# H05R2x_Frontend_1.net
KiCad netlist of a schematic drawn in Altium Designer
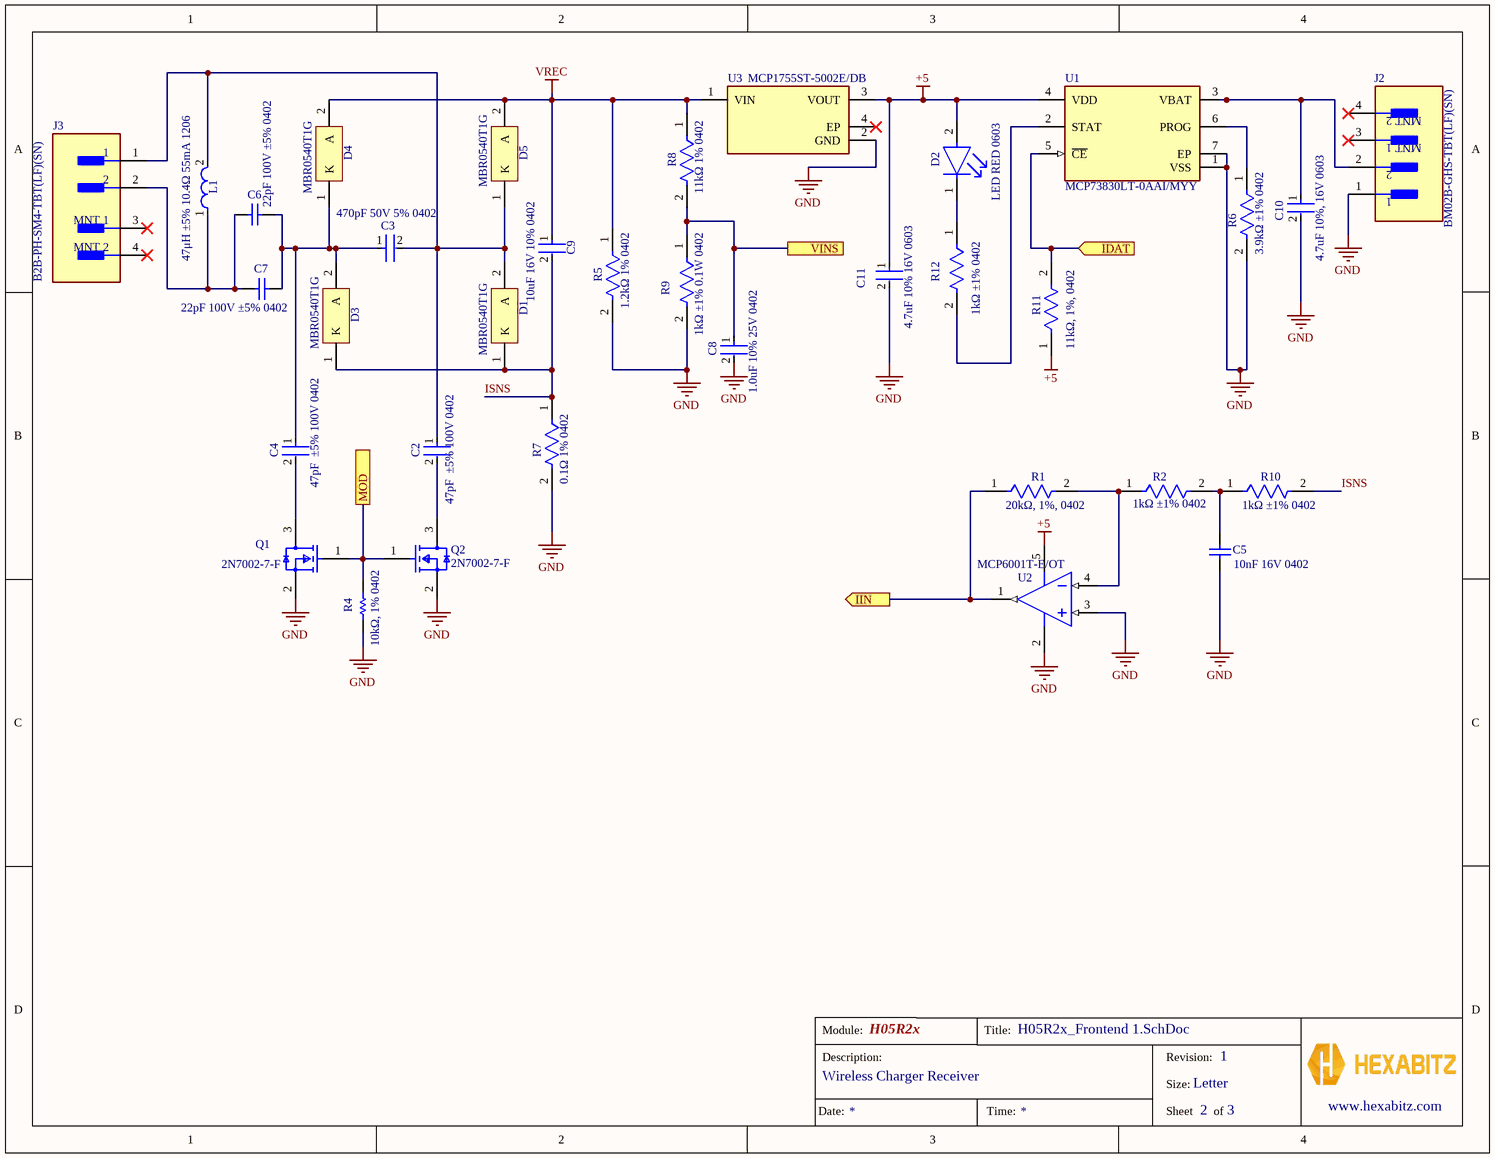
[diagram p0: H05R2x_Frontend 1.SchDoc]

(export (version "E")
  (design (tool "Eeschema 10.0.6"))
  (components
    (comp (ref "C2")
      (value "47pF  ±5% 100V 0402")
      (footprint "FP-GQM155-0_05-IPC_A")
      (description "Ceramic Capacitor 47pF  ±5% 100VDC C0G 0402 Paper T/R")
      (fields (field (name "TOLERANCE") "5%"))
      (libsource (lib "Altium Content Vault") (part "11868f565c42a9108669ba33697ecf6"))
    )
    (comp (ref "C3")
      (value "470pF 50V 5% 0402")
      (footprint "FP-C0402-BB-MFG")
      (description "C0402 470 pF C0G 0.05 50 V")
      (fields
        (field (name "MANUFACTURER PART NUMBER") "C0402C471J5GAC")
        (field (name "MANUFACTURER") "Kemet")
      )
      (libsource (lib "Altium Content Vault") (part "b4654b650e69147ec39a6b967a45e02"))
    )
    (comp (ref "C4")
      (value "47pF  ±5% 100V 0402")
      (footprint "FP-GQM155-0_05-IPC_A")
      (description "Ceramic Capacitor 47pF  ±5% 100VDC C0G 0402 Paper T/R")
      (fields (field (name "TOLERANCE") "5%"))
      (libsource (lib "Altium Content Vault") (part "11868f565c42a9108669ba33697ecf6"))
    )
    (comp (ref "C5")
      (value "10nF 16V 0402")
      (footprint "CAPC1005X60X26LL10T16")
      (fields (field (name "MANUFACTURER") "Vitramon") (field (name "PART NUMBER") "VJ0402Y103KXJAC"))
      (libsource (lib "Altium Content Vault") (part "CAP"))
    )
    (comp (ref "C6")
      (value "22pF 100V ±5% 0402")
      (footprint "CAPC1005X61X26LL10T16")
      (description "VJ0402D220JXBAJ")
      (fields (field (name "MANUFACTURER") "Vitramon"))
      (libsource (lib "Altium Content Vault") (part "CAP"))
    )
    (comp (ref "C7")
      (value "22pF 100V ±5% 0402")
      (footprint "CAPC1005X61X26LL10T16")
      (description "VJ0402D220JXBAJ")
      (fields (field (name "MANUFACTURER") "Vitramon"))
      (libsource (lib "Altium Content Vault") (part "CAP"))
    )
    (comp (ref "C8")
      (value "1.0uF 10% 25V 0402")
      (footprint "FP-GRM155-0_05-IPC_C")
      (description "Chip Multilayer Ceramic Capacitors for General Purpose, 0402, 1.0uF, B, 10%, 10%, 25V")
      (fields (field (name "TOLERANCE") "10%"))
      (libsource (lib "Altium Content Vault") (part "02cd4be3c70576c341d710602a673aa"))
    )
    (comp (ref "C9")
      (value "10uF 16V 10% 0402")
      (footprint "FP-GRM21B-0_1-IPC_B")
      (description "Chip Multilayer Ceramic Capacitors for General Purpose, 0805, 10uF, X6S, 22%, 10%, 16V")
      (fields (field (name "VOLTAGE") "16V") (field (name "TOLERANCE") "10%"))
      (libsource (lib "Altium Content Vault") (part "b4654b650e69147ec39a6b967a45e02"))
    )
    (comp (ref "C10")
      (value "4.7uF 10%, 16V 0603")
      (footprint "FP-GRM188-0_2-IPC_A")
      (description "Chip Multilayer Ceramic Capacitors for General Purpose, 0603, 4.7uF, X7S, 22%, 10%, 16V")
      (fields (field (name "TOLERANCE") "10%"))
      (libsource (lib "Altium Content Vault") (part "11868f565c42a9108669ba33697ecf6"))
    )
    (comp (ref "C11")
      (value "4.7uF 10% 16V 0603")
      (footprint "FP-GRM188-0_2-IPC_A")
      (description "Chip Multilayer Ceramic Capacitors for General Purpose, 0603, 4.7uF, X7S, 22%, 10%, 16V")
      (fields (field (name "TOLERANCE") "10%"))
      (libsource (lib "Altium Content Vault") (part "11868f565c42a9108669ba33697ecf6"))
    )
    (comp (ref "D1")
      (value "MBR0540T1G")
      (footprint "ONSC-SOD-123-2-425-04_V")
      (description "Schottky Power Rectifier, 2-Pin SOD-123, Pb-Free, Tape and Reel")
      (fields (field (name "MANUFACTURER") "On Semiconductor"))
      (libsource (lib "Altium Content Vault") (part "ONSC-D-K1A2-2_A"))
    )
    (comp (ref "D2")
      (value "LED RED 0603")
      (footprint "FP-6_541-5092_01-4-MFG")
      (description "LED RED 0603 SMD")
      (fields
        (field (name "MANUFACTURER") "Vishay")
        (field (name "MANUFACTURER PART NUMBER") "VLMS1300-GS08")
      )
      (libsource (lib "Altium Content Vault") (part "8706943c75ba83719d021d2fdc84c58"))
    )
    (comp (ref "D3")
      (value "MBR0540T1G")
      (footprint "ONSC-SOD-123-2-425-04_V")
      (description "Schottky Power Rectifier, 2-Pin SOD-123, Pb-Free, Tape and Reel")
      (fields (field (name "MANUFACTURER") "On Semiconductor"))
      (libsource (lib "Altium Content Vault") (part "ONSC-D-K1A2-2_A"))
    )
    (comp (ref "D4")
      (value "MBR0540T1G")
      (footprint "ONSC-SOD-123-2-425-04_V")
      (description "Schottky Power Rectifier, 2-Pin SOD-123, Pb-Free, Tape and Reel")
      (fields (field (name "MANUFACTURER") "On Semiconductor"))
      (libsource (lib "Altium Content Vault") (part "ONSC-D-K1A2-2_A"))
    )
    (comp (ref "D5")
      (value "MBR0540T1G")
      (footprint "ONSC-SOD-123-2-425-04_V")
      (description "Schottky Power Rectifier, 2-Pin SOD-123, Pb-Free, Tape and Reel")
      (fields (field (name "MANUFACTURER") "On Semiconductor"))
      (libsource (lib "Altium Content Vault") (part "ONSC-D-K1A2-2_A"))
    )
    (comp (ref "J2")
      (value "BM02B-GHS-TBT(LF)(SN)")
      (footprint "FP-BM02B-GHS-TBT_LF_SN-MFG")
      (description "CONN HEADER SMD 2POS 1.25MM")
      (libsource (lib "Altium Content Vault") (part "6ebc6fc72a9fd5a6899c7600f385cff"))
    )
    (comp (ref "J3")
      (value "B2B-PH-SM4-TBT(LF)(SN)")
      (footprint "FP-B2B-PH-SM4-TBT_LF_SN-MFG")
      (description "Connector Header Surface Mount 2 position 0.079\" (2.00mm)")
      (fields (field (name "OCTOPART") "https://octopart.com/b2b-ph-sm4-tbt%28lf%29%28sn%29-jst-7877930"))
      (libsource (lib "Altium Content Vault") (part "56ec3178a87b3978bdc1b3682cd516a"))
    )
    (comp (ref "L1")
      (value "47μH ±5% 10.4Ω 55mA 1206")
      (footprint "FP-LQH31CN_03-MFG")
      (description "Wire Wound Ferrite Inductor for General Circuits 47μH ±5% 10.4Ω 55mA 1206")
      (fields (field (name "TOLERANCE") "5%"))
      (libsource (lib "Altium Content Vault") (part "725321dda6339637d4d059423bc1c3c"))
    )
    (comp (ref "Q1")
      (value "2N7002-7-F")
      (footprint "FP-SOT23-MFG")
      (description "MOSFET N-CH 60V 115MA SOT23-3")
      (fields (field (name "VOLTAGE") "60V"))
      (libsource (lib "Altium Content Vault") (part "3b9c635fedb024a5347a57b145af9cc"))
    )
    (comp (ref "Q2")
      (value "2N7002-7-F")
      (footprint "FP-SOT23-MFG")
      (description "MOSFET N-CH 60V 115MA SOT23-3")
      (fields (field (name "VOLTAGE") "60V"))
      (libsource (lib "Altium Content Vault") (part "3b9c635fedb024a5347a57b145af9cc"))
    )
    (comp (ref "R1")
      (value "20kΩ, 1%, 0402")
      (footprint "FP-TFCR0402-IPC_A")
      (description "RES Thin Film,  20kΩ, 1%, 0.063W, 50ppm/°C, 0402")
      (libsource (lib "Altium Content Vault") (part "1029c3af85768c4190bb7ad29bc67b5"))
    )
    (comp (ref "R2")
      (value "1kΩ ±1% 0402")
      (footprint "FP-RNCP0402-IPC_C")
      (description "1kΩ ±1% 0.1W 0402 High Power Anti-Sulfur Thin Film Chip Resistor")
      (fields (field (name "TOLERANCE") "1%"))
      (libsource (lib "Altium Content Vault") (part "1029c3af85768c4190bb7ad29bc67b5"))
    )
    (comp (ref "R4")
      (value "10kΩ, 1% 0402")
      (footprint "RESC1005X40X25LL10T10")
      (fields (field (name "MANUFACTURER") "KOA Speer") (field (name "PART NUMBER") "SG73P1ETTP1002F"))
      (libsource (lib "Altium Content Vault") (part "RES"))
    )
    (comp (ref "R5")
      (value "1.2kΩ 1% 0402")
      (footprint "FP-MCS0402-IPC_C")
      (description "RES SMD 1.2K OHM 1% 1/10W 0402")
      (fields (field (name "TOLERANCE") "1%"))
      (libsource (lib "Altium Content Vault") (part "1029c3af85768c4190bb7ad29bc67b5"))
    )
    (comp (ref "R6")
      (value "3.9kΩ ±1% 0402")
      (footprint "FP-RN73R1E-IPC_C")
      (description "3.9kΩ ±1% 0.063W, 1/16W Chip Resistor 0402 (1005 Metric) Moisture Resistant Thin Film")
      (libsource (lib "Altium Content Vault") (part "1029c3af85768c4190bb7ad29bc67b5"))
    )
    (comp (ref "R7")
      (value "0.1Ω 1% 0402")
      (footprint "FP-CSR0402-IPC_A")
      (description "General Purpose Thick Film Chip Resistor, 0402, 0.1Ω, 1%, 200ppm/°C, 0.125W")
      (fields (field (name "TOLERANCE") "1%"))
      (libsource (lib "Altium Content Vault") (part "1029c3af85768c4190bb7ad29bc67b5"))
    )
    (comp (ref "R8")
      (value "11kΩ 1% 0402")
      (footprint "FP-CRCW0402-e3-IPC_B")
      (description "RES Thick Film, 11kΩ, 1%, 0.063W, 100ppm/°C, 0402")
      (fields (field (name "TOLERANCE") "1%"))
      (libsource (lib "Altium Content Vault") (part "1029c3af85768c4190bb7ad29bc67b5"))
    )
    (comp (ref "R9")
      (value "1kΩ ±1% 0.1W 0402")
      (footprint "FP-RNCP0402-IPC_C")
      (description "1kΩ ±1% 0.1W 0402 High Power Anti-Sulfur Thin Film Chip Resistor")
      (fields (field (name "TOLERANCE") "1%"))
      (libsource (lib "Altium Content Vault") (part "1029c3af85768c4190bb7ad29bc67b5"))
    )
    (comp (ref "R10")
      (value "1kΩ ±1% 0402")
      (footprint "FP-RNCP0402-IPC_C")
      (description "1kΩ ±1% 0.1W 0402 High Power Anti-Sulfur Thin Film Chip Resistor")
      (fields (field (name "TOLERANCE") "1%"))
      (libsource (lib "Altium Content Vault") (part "1029c3af85768c4190bb7ad29bc67b5"))
    )
    (comp (ref "R11")
      (value "11kΩ, 1%, 0402")
      (footprint "FP-CRCW0402-e3-IPC_B")
      (description "RES Thick Film, 11kΩ, 1%, 0.063W, 100ppm/°C, 0402")
      (fields (field (name "TOLERANCE") "1%"))
      (libsource (lib "Altium Content Vault") (part "1029c3af85768c4190bb7ad29bc67b5"))
    )
    (comp (ref "R12")
      (value "1kΩ ±1% 0402")
      (footprint "FP-AC0402-IPC_C")
      (description "RES 1kΩ ±1% 0.063W 0402")
      (libsource (lib "Altium Content Vault") (part "1029c3af85768c4190bb7ad29bc67b5"))
    )
    (comp (ref "U1")
      (value "MCP73830LT-0AAI/MYY")
      (footprint "FP-C04-078-IPC_C")
      (description "IC BATT CHG LI-ION 1CELL 6TDFN")
      (libsource (lib "Altium Content Vault") (part "eab4c6cdc0eba9ee105b8b64542a710"))
    )
    (comp (ref "U2")
      (value "MCP6001T-E/OT")
      (footprint "SOT-23-OT5_L")
      (description "None")
      (fields (field (name "VOLTAGE") "6V"))
      (libsource (lib "Altium Content Vault") (part "AMP-OPA-MCP6001-SOT5"))
    )
    (comp (ref "U3")
      (value "MCP1755ST-5002E/DB")
      (footprint "FP-C04-032-IPC_B")
      (description "IC REG LINEAR 5V 300MA SOT223-3")
      (libsource (lib "Altium Content Vault") (part "0edcb772792940466765807cac25de9"))
    )
  )
  (nets
    (net (code "1") (name "+5") (class "Default")
      (node (ref "C11") (pin "1") (pinfunction "1_1") (pintype "passive"))
      (node (ref "D2") (pin "2") (pinfunction "A_2") (pintype "passive"))
      (node (ref "R11") (pin "1") (pinfunction "1_1") (pintype "passive"))
      (node (ref "U1") (pin "4") (pinfunction "VDD_4") (pintype "power_in"))
      (node (ref "U2") (pin "5") (pinfunction "VDD_5") (pintype "power_in"))
      (node (ref "U3") (pin "3") (pinfunction "VOUT_3") (pintype "passive"))
    )
    (net (code "2") (name "/IDAT") (class "Default")
      (node (ref "R11") (pin "2") (pinfunction "2_2") (pintype "passive"))
      (node (ref "U1") (pin "5") (pinfunction "~{CE}_5") (pintype "input"))
    )
    (net (code "3") (name "/IIN") (class "Default")
      (node (ref "R1") (pin "1") (pinfunction "1_1") (pintype "passive"))
      (node (ref "U2") (pin "1") (pinfunction "VOUT_1") (pintype "output"))
    )
    (net (code "4") (name "/ISNS") (class "Default")
      (node (ref "C9") (pin "2") (pinfunction "2_2") (pintype "passive"))
      (node (ref "D1") (pin "1") (pinfunction "K_1") (pintype "passive"))
      (node (ref "D3") (pin "1") (pinfunction "K_1") (pintype "passive"))
      (node (ref "R10") (pin "2") (pinfunction "2_2") (pintype "passive"))
      (node (ref "R7") (pin "1") (pinfunction "1_1") (pintype "passive"))
    )
    (net (code "5") (name "/MOD") (class "Default")
      (node (ref "Q1") (pin "1") (pinfunction "G_1") (pintype "passive"))
      (node (ref "Q2") (pin "1") (pinfunction "G_1") (pintype "passive"))
      (node (ref "R4") (pin "2") (pinfunction "2_2") (pintype "passive"))
    )
    (net (code "6") (name "/VINS") (class "Default")
      (node (ref "C8") (pin "1") (pinfunction "1_1") (pintype "passive"))
      (node (ref "R8") (pin "2") (pinfunction "2_2") (pintype "passive"))
      (node (ref "R9") (pin "1") (pinfunction "1_1") (pintype "passive"))
    )
    (net (code "7") (name "GND") (class "Default")
      (node (ref "C10") (pin "2") (pinfunction "2_2") (pintype "passive"))
      (node (ref "C11") (pin "2") (pinfunction "2_2") (pintype "passive"))
      (node (ref "C5") (pin "2") (pinfunction "2_2") (pintype "passive"))
      (node (ref "C8") (pin "2") (pinfunction "2_2") (pintype "passive"))
      (node (ref "J2") (pin "1") (pinfunction "1_1") (pintype "passive"))
      (node (ref "Q1") (pin "2") (pinfunction "S_2") (pintype "passive"))
      (node (ref "Q2") (pin "2") (pinfunction "S_2") (pintype "passive"))
      (node (ref "R4") (pin "1") (pinfunction "1_1") (pintype "passive"))
      (node (ref "R5") (pin "2") (pinfunction "2_2") (pintype "passive"))
      (node (ref "R6") (pin "2") (pinfunction "2_2") (pintype "passive"))
      (node (ref "R7") (pin "2") (pinfunction "2_2") (pintype "passive"))
      (node (ref "R9") (pin "2") (pinfunction "2_2") (pintype "passive"))
      (node (ref "U1") (pin "1") (pinfunction "VSS_1") (pintype "power_in"))
      (node (ref "U1") (pin "7") (pinfunction "EP_7") (pintype "power_in"))
      (node (ref "U2") (pin "2") (pinfunction "VSS_2") (pintype "power_in"))
      (node (ref "U2") (pin "3") (pinfunction "VIN+_3") (pintype "input"))
      (node (ref "U3") (pin "2") (pinfunction "GND_2") (pintype "power_in"))
    )
    (net (code "8") (name "Net-(C5-Pad1)") (class "Default")
      (node (ref "C5") (pin "1") (pinfunction "1_1") (pintype "passive"))
      (node (ref "R10") (pin "1") (pinfunction "1_1") (pintype "passive"))
      (node (ref "R2") (pin "2") (pinfunction "2_2") (pintype "passive"))
    )
    (net (code "9") (name "Net-(C6-Pad1)") (class "Default")
      (node (ref "C6") (pin "1") (pinfunction "1_1") (pintype "passive"))
      (node (ref "C7") (pin "1") (pinfunction "1_1") (pintype "passive"))
      (node (ref "J3") (pin "2") (pinfunction "2_2") (pintype "passive"))
      (node (ref "L1") (pin "1") (pinfunction "1_1") (pintype "passive"))
    )
    (net (code "10") (name "Net-(D1-A)") (class "Default")
      (node (ref "C2") (pin "1") (pinfunction "1_1") (pintype "passive"))
      (node (ref "C3") (pin "2") (pinfunction "2_2") (pintype "passive"))
      (node (ref "D1") (pin "2") (pinfunction "A_2") (pintype "passive"))
      (node (ref "D5") (pin "1") (pinfunction "K_1") (pintype "passive"))
      (node (ref "J3") (pin "1") (pinfunction "1_1") (pintype "passive"))
      (node (ref "L1") (pin "2") (pinfunction "2_2") (pintype "passive"))
    )
    (net (code "11") (name "Net-(D2-C)") (class "Default")
      (node (ref "D2") (pin "1") (pinfunction "C_1") (pintype "passive"))
      (node (ref "R12") (pin "1") (pinfunction "1_1") (pintype "passive"))
    )
    (net (code "12") (name "Net-(D3-A)") (class "Default")
      (node (ref "C3") (pin "1") (pinfunction "1_1") (pintype "passive"))
      (node (ref "C4") (pin "1") (pinfunction "1_1") (pintype "passive"))
      (node (ref "C6") (pin "2") (pinfunction "2_2") (pintype "passive"))
      (node (ref "C7") (pin "2") (pinfunction "2_2") (pintype "passive"))
      (node (ref "D3") (pin "2") (pinfunction "A_2") (pintype "passive"))
      (node (ref "D4") (pin "1") (pinfunction "K_1") (pintype "passive"))
    )
    (net (code "13") (name "Net-(Q1-D)") (class "Default")
      (node (ref "C4") (pin "2") (pinfunction "2_2") (pintype "passive"))
      (node (ref "Q1") (pin "3") (pinfunction "D_3") (pintype "passive"))
    )
    (net (code "14") (name "Net-(Q2-D)") (class "Default")
      (node (ref "C2") (pin "2") (pinfunction "2_2") (pintype "passive"))
      (node (ref "Q2") (pin "3") (pinfunction "D_3") (pintype "passive"))
    )
    (net (code "15") (name "Net-(U1-PROG)") (class "Default")
      (node (ref "R6") (pin "1") (pinfunction "1_1") (pintype "passive"))
      (node (ref "U1") (pin "6") (pinfunction "PROG_6") (pintype "passive"))
    )
    (net (code "16") (name "Net-(U1-STAT)") (class "Default")
      (node (ref "R12") (pin "2") (pinfunction "2_2") (pintype "passive"))
      (node (ref "U1") (pin "2") (pinfunction "STAT_2") (pintype "passive"))
    )
    (net (code "17") (name "Net-(U1-VBAT)") (class "Default")
      (node (ref "C10") (pin "1") (pinfunction "1_1") (pintype "passive"))
      (node (ref "J2") (pin "2") (pinfunction "2_2") (pintype "passive"))
      (node (ref "U1") (pin "3") (pinfunction "VBAT_3") (pintype "power_in"))
    )
    (net (code "18") (name "Net-(U2-VIN-)") (class "Default")
      (node (ref "R1") (pin "2") (pinfunction "2_2") (pintype "passive"))
      (node (ref "R2") (pin "1") (pinfunction "1_1") (pintype "passive"))
      (node (ref "U2") (pin "4") (pinfunction "VIN-_4") (pintype "input"))
    )
    (net (code "19") (name "VREC") (class "Default")
      (node (ref "C9") (pin "1") (pinfunction "1_1") (pintype "passive"))
      (node (ref "D4") (pin "2") (pinfunction "A_2") (pintype "passive"))
      (node (ref "D5") (pin "2") (pinfunction "A_2") (pintype "passive"))
      (node (ref "R5") (pin "1") (pinfunction "1_1") (pintype "passive"))
      (node (ref "R8") (pin "1") (pinfunction "1_1") (pintype "passive"))
      (node (ref "U3") (pin "1") (pinfunction "VIN_1") (pintype "power_in"))
    )
    (net (code "20") (name "unconnected-(J2-MNT_1-Pad3)") (class "Default")
      (node (ref "J2") (pin "3") (pinfunction "MNT_1_3") (pintype "passive+no_connect"))
    )
    (net (code "21") (name "unconnected-(J2-MNT_2-Pad4)") (class "Default")
      (node (ref "J2") (pin "4") (pinfunction "MNT_2_4") (pintype "passive+no_connect"))
    )
    (net (code "22") (name "unconnected-(J3-MNT_1-Pad3)") (class "Default")
      (node (ref "J3") (pin "3") (pinfunction "MNT_1_3") (pintype "passive+no_connect"))
    )
    (net (code "23") (name "unconnected-(J3-MNT_2-Pad4)") (class "Default")
      (node (ref "J3") (pin "4") (pinfunction "MNT_2_4") (pintype "passive+no_connect"))
    )
    (net (code "24") (name "unconnected-(U3-EP-Pad4)") (class "Default")
      (node (ref "U3") (pin "4") (pinfunction "EP_4") (pintype "passive+no_connect"))
    )
  )
)
